# Sheet1.net
KiCad netlist of a schematic drawn in Altium Designer
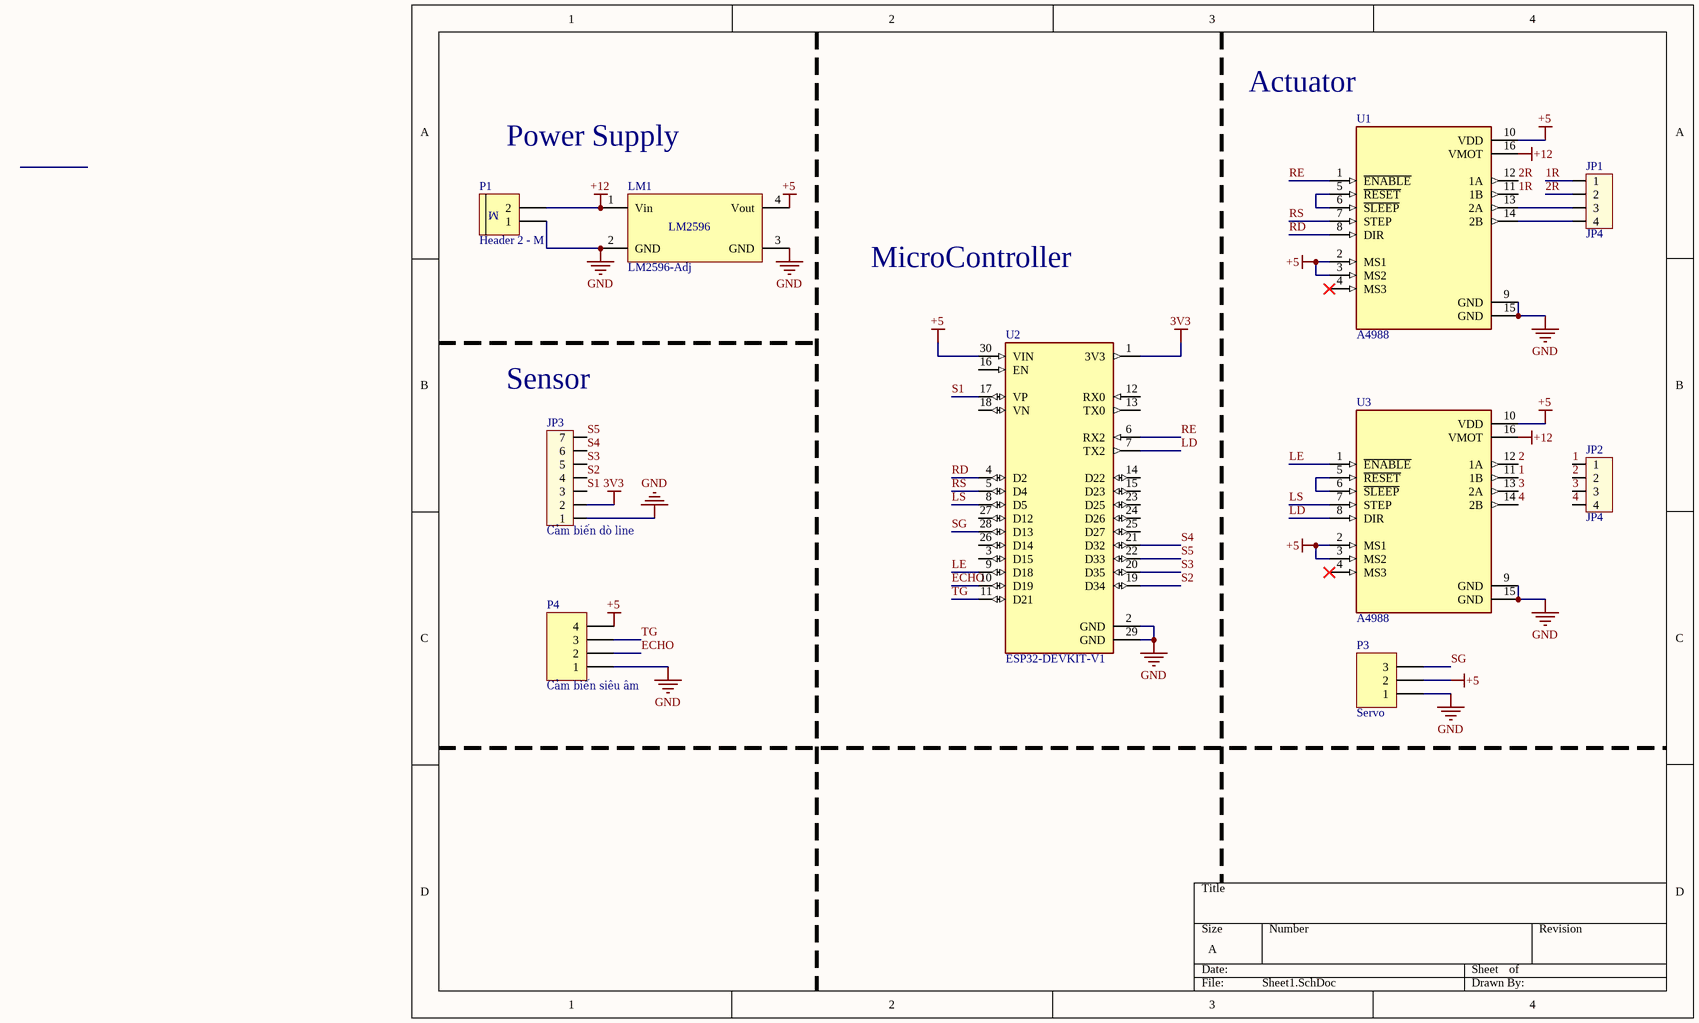
[diagram p0: Sheet1.SchDoc]

(export (version "E")
  (design (tool "Eeschema 10.0.6"))
  (components
    (comp (ref "JP1")
      (value "JP4")
      (footprint "CON4")
      (description "Connector 4")
      (libsource (lib "Kiet") (part "Con4"))
    )
    (comp (ref "JP2")
      (value "JP4")
      (footprint "CON4")
      (description "Connector 4")
      (libsource (lib "Kiet") (part "Con4"))
    )
    (comp (ref "JP3")
      (value "Cảm biến dò line")
      (footprint "CON7")
      (description "Connector 7")
      (libsource (lib "Kiet") (part "Con7"))
    )
    (comp (ref "LM1")
      (value "LM2596-Adj")
      (footprint "lm2596")
      (description "Designed By @Alixahedi")
      (libsource (lib "LM2596-Adj") (part "LM2596-Adj"))
    )
    (comp (ref "P1")
      (value "Header 2 - M")
      (footprint "Medium - Header 2")
      (description "Header, 2-Pin, Medium")
      (fields (field (name "PUBLISHER") "Altium Limited"))
      (libsource (lib "Kiet") (part "Header 2 - M"))
    )
    (comp (ref "P3")
      (value "Servo")
      (footprint "Header 3")
      (description "Header, 3-Pin")
      (fields (field (name "PUBLISHER") "Altium Limited"))
      (libsource (lib "Kiet") (part "Header 3"))
    )
    (comp (ref "P4")
      (value "Cảm biến siêu âm")
      (footprint "Header 4")
      (description "Header, 4-Pin")
      (fields (field (name "PUBLISHER") "Altium Limited"))
      (libsource (lib "Kiet") (part "Header 4"))
    )
    (comp (ref "U1")
      (value "A4988")
      (footprint "MODULE_A4988_STEPPER_MOTOR_DRIVER_CARRIER")
      (description "Stepper motor controler; IC: A4988; 1A; Uin mot: 8Ã·35V")
      (fields (field (name "MP") "A4988_STEPPER_MOTOR_DRIVER_CARRIER"))
      (libsource (lib "A4988_STEPPER_MOTOR_DRIVER_CARRIER") (part "A4988_STEPPER_MOTOR_DRIVER_CARRIER"))
    )
    (comp (ref "U2")
      (value "ESP32-DEVKIT-V1")
      (footprint "MODULE_ESP32_DEVKIT_V1")
      (fields (field (name "MF") "Do it"))
      (libsource (lib "ESP32-DEVKIT-V1") (part "ESP32-DEVKIT-V1"))
    )
    (comp (ref "U3")
      (value "A4988")
      (footprint "MODULE_A4988_STEPPER_MOTOR_DRIVER_CARRIER")
      (description "Stepper motor controler; IC: A4988; 1A; Uin mot: 8Ã·35V")
      (fields (field (name "MP") "A4988_STEPPER_MOTOR_DRIVER_CARRIER"))
      (libsource (lib "A4988_STEPPER_MOTOR_DRIVER_CARRIER") (part "A4988_STEPPER_MOTOR_DRIVER_CARRIER"))
    )
  )
  (nets
    (net (code "1") (name "+5") (class "Default")
      (node (ref "LM1") (pin "4") (pinfunction "Vout_4") (pintype "passive"))
      (node (ref "P3") (pin "2") (pinfunction "2_2") (pintype "passive"))
      (node (ref "P4") (pin "4") (pinfunction "4_4") (pintype "passive"))
      (node (ref "U1") (pin "10") (pinfunction "VDD_10") (pintype "power_in"))
      (node (ref "U1") (pin "2") (pinfunction "MS1_2") (pintype "input"))
      (node (ref "U1") (pin "3") (pinfunction "MS2_3") (pintype "input"))
      (node (ref "U2") (pin "30") (pinfunction "VIN_30") (pintype "input"))
      (node (ref "U3") (pin "10") (pinfunction "VDD_10") (pintype "power_in"))
      (node (ref "U3") (pin "2") (pinfunction "MS1_2") (pintype "input"))
      (node (ref "U3") (pin "3") (pinfunction "MS2_3") (pintype "input"))
    )
    (net (code "2") (name "+12") (class "Default")
      (node (ref "LM1") (pin "1") (pinfunction "Vin_1") (pintype "passive"))
      (node (ref "P1") (pin "2") (pinfunction "2_2") (pintype "passive"))
      (node (ref "U1") (pin "16") (pinfunction "VMOT_16") (pintype "power_in"))
      (node (ref "U3") (pin "16") (pinfunction "VMOT_16") (pintype "power_in"))
    )
    (net (code "3") (name "/1") (class "Default")
      (node (ref "JP2") (pin "1") (pinfunction "1_1") (pintype "passive"))
      (node (ref "U3") (pin "11") (pinfunction "1B_11") (pintype "output"))
    )
    (net (code "4") (name "/1R") (class "Default")
      (node (ref "JP1") (pin "1") (pinfunction "1_1") (pintype "passive"))
      (node (ref "U1") (pin "11") (pinfunction "1B_11") (pintype "output"))
    )
    (net (code "5") (name "/2") (class "Default")
      (node (ref "JP2") (pin "2") (pinfunction "2_2") (pintype "passive"))
      (node (ref "U3") (pin "12") (pinfunction "1A_12") (pintype "output"))
    )
    (net (code "6") (name "/2R") (class "Default")
      (node (ref "JP1") (pin "2") (pinfunction "2_2") (pintype "passive"))
      (node (ref "U1") (pin "12") (pinfunction "1A_12") (pintype "output"))
    )
    (net (code "7") (name "/3") (class "Default")
      (node (ref "JP2") (pin "3") (pinfunction "3_3") (pintype "passive"))
      (node (ref "U3") (pin "13") (pinfunction "2A_13") (pintype "output"))
    )
    (net (code "8") (name "/4") (class "Default")
      (node (ref "JP2") (pin "4") (pinfunction "4_4") (pintype "passive"))
      (node (ref "U3") (pin "14") (pinfunction "2B_14") (pintype "output"))
    )
    (net (code "9") (name "/ECHO") (class "Default")
      (node (ref "P4") (pin "2") (pinfunction "2_2") (pintype "passive"))
      (node (ref "U2") (pin "10") (pinfunction "D19_10") (pintype "bidirectional"))
    )
    (net (code "10") (name "/LD") (class "Default")
      (node (ref "U2") (pin "7") (pinfunction "TX2_7") (pintype "output"))
      (node (ref "U3") (pin "8") (pinfunction "DIR_8") (pintype "input"))
    )
    (net (code "11") (name "/LE") (class "Default")
      (node (ref "U2") (pin "9") (pinfunction "D18_9") (pintype "bidirectional"))
      (node (ref "U3") (pin "1") (pinfunction "~{ENABLE}_1") (pintype "input"))
    )
    (net (code "12") (name "/LS") (class "Default")
      (node (ref "U2") (pin "8") (pinfunction "D5_8") (pintype "bidirectional"))
      (node (ref "U3") (pin "7") (pinfunction "STEP_7") (pintype "input"))
    )
    (net (code "13") (name "/RD") (class "Default")
      (node (ref "U1") (pin "8") (pinfunction "DIR_8") (pintype "input"))
      (node (ref "U2") (pin "4") (pinfunction "D2_4") (pintype "bidirectional"))
    )
    (net (code "14") (name "/RE") (class "Default")
      (node (ref "U1") (pin "1") (pinfunction "~{ENABLE}_1") (pintype "input"))
      (node (ref "U2") (pin "6") (pinfunction "RX2_6") (pintype "input"))
    )
    (net (code "15") (name "/RS") (class "Default")
      (node (ref "U1") (pin "7") (pinfunction "STEP_7") (pintype "input"))
      (node (ref "U2") (pin "5") (pinfunction "D4_5") (pintype "bidirectional"))
    )
    (net (code "16") (name "/S1") (class "Default")
      (node (ref "JP3") (pin "3") (pinfunction "3_3") (pintype "passive"))
      (node (ref "U2") (pin "17") (pinfunction "VP_17") (pintype "bidirectional"))
    )
    (net (code "17") (name "/S2") (class "Default")
      (node (ref "JP3") (pin "4") (pinfunction "4_4") (pintype "passive"))
      (node (ref "U2") (pin "19") (pinfunction "D34_19") (pintype "bidirectional"))
    )
    (net (code "18") (name "/S3") (class "Default")
      (node (ref "JP3") (pin "5") (pinfunction "5_5") (pintype "passive"))
      (node (ref "U2") (pin "20") (pinfunction "D35_20") (pintype "bidirectional"))
    )
    (net (code "19") (name "/S4") (class "Default")
      (node (ref "JP3") (pin "6") (pinfunction "6_6") (pintype "passive"))
      (node (ref "U2") (pin "21") (pinfunction "D32_21") (pintype "bidirectional"))
    )
    (net (code "20") (name "/S5") (class "Default")
      (node (ref "JP3") (pin "7") (pinfunction "7_7") (pintype "passive"))
      (node (ref "U2") (pin "22") (pinfunction "D33_22") (pintype "bidirectional"))
    )
    (net (code "21") (name "/SG") (class "Default")
      (node (ref "P3") (pin "3") (pinfunction "3_3") (pintype "passive"))
      (node (ref "U2") (pin "28") (pinfunction "D13_28") (pintype "bidirectional"))
    )
    (net (code "22") (name "/TG") (class "Default")
      (node (ref "P4") (pin "3") (pinfunction "3_3") (pintype "passive"))
      (node (ref "U2") (pin "11") (pinfunction "D21_11") (pintype "bidirectional"))
    )
    (net (code "23") (name "3V3") (class "Default")
      (node (ref "JP3") (pin "2") (pinfunction "2_2") (pintype "passive"))
      (node (ref "U2") (pin "1") (pinfunction "3V3_1") (pintype "output"))
    )
    (net (code "24") (name "GND") (class "Default")
      (node (ref "JP3") (pin "1") (pinfunction "1_1") (pintype "passive"))
      (node (ref "LM1") (pin "2") (pinfunction "GND_2") (pintype "passive"))
      (node (ref "LM1") (pin "3") (pinfunction "GND_3") (pintype "passive"))
      (node (ref "P1") (pin "1") (pinfunction "1_1") (pintype "passive"))
      (node (ref "P3") (pin "1") (pinfunction "1_1") (pintype "passive"))
      (node (ref "P4") (pin "1") (pinfunction "1_1") (pintype "passive"))
      (node (ref "U1") (pin "15") (pinfunction "GND_15") (pintype "power_in"))
      (node (ref "U1") (pin "9") (pinfunction "GND_9") (pintype "power_in"))
      (node (ref "U2") (pin "2") (pinfunction "GND_2") (pintype "power_in"))
      (node (ref "U2") (pin "29") (pinfunction "GND_29") (pintype "power_in"))
      (node (ref "U3") (pin "15") (pinfunction "GND_15") (pintype "power_in"))
      (node (ref "U3") (pin "9") (pinfunction "GND_9") (pintype "power_in"))
    )
    (net (code "25") (name "Net-(U1-2A)") (class "Default")
      (node (ref "JP1") (pin "3") (pinfunction "3_3") (pintype "passive"))
      (node (ref "U1") (pin "13") (pinfunction "2A_13") (pintype "output"))
    )
    (net (code "26") (name "Net-(U1-2B)") (class "Default")
      (node (ref "JP1") (pin "4") (pinfunction "4_4") (pintype "passive"))
      (node (ref "U1") (pin "14") (pinfunction "2B_14") (pintype "output"))
    )
    (net (code "27") (name "Net-(U1-~{RESET})") (class "Default")
      (node (ref "U1") (pin "5") (pinfunction "~{RESET}_5") (pintype "input"))
      (node (ref "U1") (pin "6") (pinfunction "~{SLEEP}_6") (pintype "input"))
    )
    (net (code "28") (name "Net-(U3-~{RESET})") (class "Default")
      (node (ref "U3") (pin "5") (pinfunction "~{RESET}_5") (pintype "input"))
      (node (ref "U3") (pin "6") (pinfunction "~{SLEEP}_6") (pintype "input"))
    )
    (net (code "29") (name "unconnected-(U1-MS3-Pad4)") (class "Default")
      (node (ref "U1") (pin "4") (pinfunction "MS3_4") (pintype "input+no_connect"))
    )
    (net (code "30") (name "unconnected-(U2-D12-Pad27)") (class "Default")
      (node (ref "U2") (pin "27") (pinfunction "D12_27") (pintype "bidirectional"))
    )
    (net (code "31") (name "unconnected-(U2-D14-Pad26)") (class "Default")
      (node (ref "U2") (pin "26") (pinfunction "D14_26") (pintype "bidirectional"))
    )
    (net (code "32") (name "unconnected-(U2-D15-Pad3)") (class "Default")
      (node (ref "U2") (pin "3") (pinfunction "D15_3") (pintype "bidirectional"))
    )
    (net (code "33") (name "unconnected-(U2-D22-Pad14)") (class "Default")
      (node (ref "U2") (pin "14") (pinfunction "D22_14") (pintype "bidirectional"))
    )
    (net (code "34") (name "unconnected-(U2-D23-Pad15)") (class "Default")
      (node (ref "U2") (pin "15") (pinfunction "D23_15") (pintype "bidirectional"))
    )
    (net (code "35") (name "unconnected-(U2-D25-Pad23)") (class "Default")
      (node (ref "U2") (pin "23") (pinfunction "D25_23") (pintype "bidirectional"))
    )
    (net (code "36") (name "unconnected-(U2-D26-Pad24)") (class "Default")
      (node (ref "U2") (pin "24") (pinfunction "D26_24") (pintype "bidirectional"))
    )
    (net (code "37") (name "unconnected-(U2-D27-Pad25)") (class "Default")
      (node (ref "U2") (pin "25") (pinfunction "D27_25") (pintype "bidirectional"))
    )
    (net (code "38") (name "unconnected-(U2-EN-Pad16)") (class "Default")
      (node (ref "U2") (pin "16") (pinfunction "EN_16") (pintype "input"))
    )
    (net (code "39") (name "unconnected-(U2-RX0-Pad12)") (class "Default")
      (node (ref "U2") (pin "12") (pinfunction "RX0_12") (pintype "input"))
    )
    (net (code "40") (name "unconnected-(U2-TX0-Pad13)") (class "Default")
      (node (ref "U2") (pin "13") (pinfunction "TX0_13") (pintype "output"))
    )
    (net (code "41") (name "unconnected-(U2-VN-Pad18)") (class "Default")
      (node (ref "U2") (pin "18") (pinfunction "VN_18") (pintype "bidirectional"))
    )
    (net (code "42") (name "unconnected-(U3-MS3-Pad4)") (class "Default")
      (node (ref "U3") (pin "4") (pinfunction "MS3_4") (pintype "input+no_connect"))
    )
  )
)
